# MicroMySens-v015.net
KiCad netlist of a schematic drawn in EAGLE
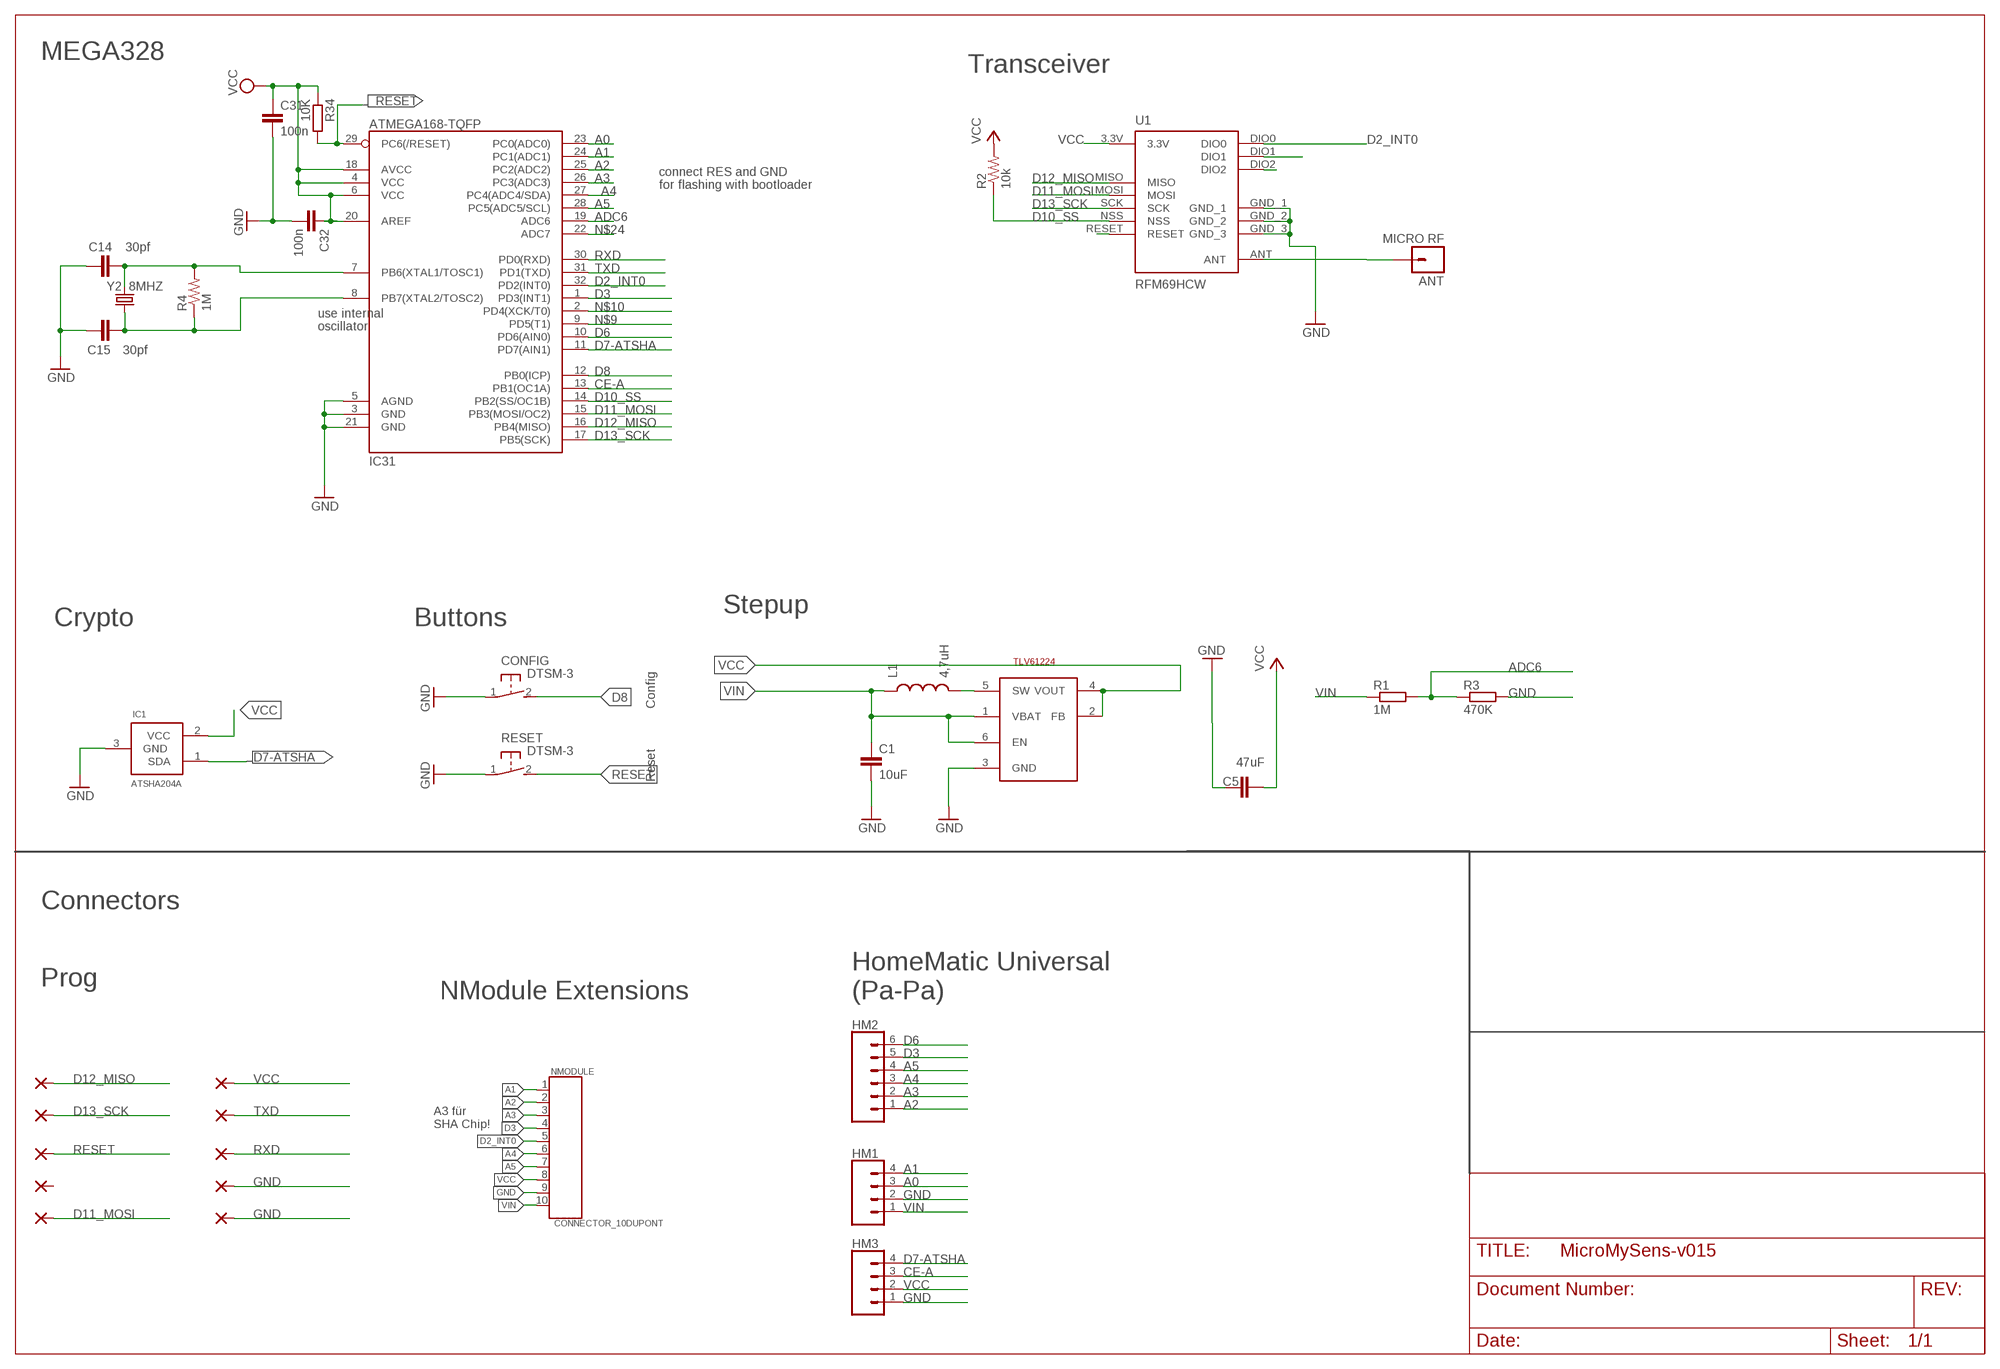
[diagram p0: schematic, sheet 1]

(export (version "E")
  (design (tool "Eeschema 10.0.6"))
  (components
    (comp (ref "ANT")
      (value "MICRO RF")
      (footprint "eagle-import:1X01")
      (libsource (lib "eagle-import") (part "M01PTH"))
    )
    (comp (ref "C1")
      (value "10uF")
      (footprint "eagle-import:0805")
      (libsource (lib "eagle-import") (part "CAP0805"))
    )
    (comp (ref "C5")
      (value "47uF")
      (footprint "eagle-import:C1210")
      (libsource (lib "eagle-import") (part "C-EUC1210"))
    )
    (comp (ref "C14")
      (value "30pf")
      (footprint "eagle-import:0805")
      (libsource (lib "eagle-import") (part "doug_CAP0805"))
    )
    (comp (ref "C15")
      (value "30pf")
      (footprint "eagle-import:0805")
      (libsource (lib "eagle-import") (part "doug_CAP0805"))
    )
    (comp (ref "C31")
      (value "100n")
      (footprint "eagle-import:C0805")
      (libsource (lib "eagle-import") (part "C-EUC0805"))
    )
    (comp (ref "C32")
      (value "100n")
      (footprint "eagle-import:C0805")
      (libsource (lib "eagle-import") (part "C-EUC0805"))
    )
    (comp (ref "CONFIG")
      (value "DTSM-3")
      (footprint "eagle-import:DTSM-3")
      (libsource (lib "eagle-import") (part "DTSM-3"))
    )
    (comp (ref "GND")
      (value "WIREPADSMD1,27-254")
      (footprint "eagle-import:SMD1,27-2,54")
      (libsource (lib "eagle-import") (part "WIREPADSMD1,27-254"))
    )
    (comp (ref "GND2")
      (value "WIREPADSMD1,27-254")
      (footprint "eagle-import:SMD1,27-2,54")
      (libsource (lib "eagle-import") (part "WIREPADSMD1,27-254"))
    )
    (comp (ref "HM1")
      (value "CONN_04")
      (footprint "eagle-import:1X04")
      (libsource (lib "eagle-import") (part "CONN_04"))
    )
    (comp (ref "HM2")
      (value "CONN_06SILK_FEMALE_PTH")
      (footprint "eagle-import:1X06")
      (libsource (lib "eagle-import") (part "CONN_06SILK_FEMALE_PTH"))
    )
    (comp (ref "HM3")
      (value "CONN_04")
      (footprint "eagle-import:1X04")
      (libsource (lib "eagle-import") (part "CONN_04"))
    )
    (comp (ref "IC1")
      (value "ATSHA204A")
      (footprint "eagle-import:SOT23")
      (libsource (lib "eagle-import") (part "ATSHA204A"))
    )
    (comp (ref "IC31")
      (value "ATMEGA168-TQFP")
      (footprint "eagle-import:TQFP32-08")
      (libsource (lib "eagle-import") (part "ATMEGA168-TQFP"))
    )
    (comp (ref "L1")
      (value "4,7uH")
      (footprint "eagle-import:0805")
      (libsource (lib "eagle-import") (part "INDUCTOR0805"))
    )
    (comp (ref "MISO")
      (value "WIREPADSMD1,27-254")
      (footprint "eagle-import:SMD1,27-2,54")
      (libsource (lib "eagle-import") (part "WIREPADSMD1,27-254"))
    )
    (comp (ref "MOSI")
      (value "WIREPADSMD1,27-254")
      (footprint "eagle-import:SMD1,27-2,54")
      (libsource (lib "eagle-import") (part "WIREPADSMD1,27-254"))
    )
    (comp (ref "NC")
      (value "WIREPADSMD1,27-254")
      (footprint "eagle-import:SMD1,27-2,54")
      (libsource (lib "eagle-import") (part "WIREPADSMD1,27-254"))
    )
    (comp (ref "NMODULE")
      (value "CONNECTOR_10DUPONT")
      (footprint "eagle-import:DUPONT_10")
      (libsource (lib "eagle-import") (part "CONNECTOR_10DUPONT"))
    )
    (comp (ref "R1")
      (value "1M")
      (footprint "eagle-import:R0805")
      (libsource (lib "eagle-import") (part "R-EU_R0805"))
    )
    (comp (ref "R2")
      (value "10k")
      (footprint "eagle-import:0805")
      (libsource (lib "eagle-import") (part "RESISTOR0805-RES"))
    )
    (comp (ref "R3")
      (value "470K")
      (footprint "eagle-import:R0805")
      (libsource (lib "eagle-import") (part "R-EU_R0805"))
    )
    (comp (ref "R4")
      (value "1M")
      (footprint "eagle-import:0805")
      (libsource (lib "eagle-import") (part "RESISTOR0805-RES"))
    )
    (comp (ref "R34")
      (value "10K")
      (footprint "eagle-import:R0805")
      (libsource (lib "eagle-import") (part "R-EU_R0805"))
    )
    (comp (ref "RESET")
      (value "DTSM-3")
      (footprint "eagle-import:DTSM-3")
      (libsource (lib "eagle-import") (part "DTSM-3"))
    )
    (comp (ref "RST")
      (value "WIREPADSMD1,27-254")
      (footprint "eagle-import:SMD1,27-2,54")
      (libsource (lib "eagle-import") (part "WIREPADSMD1,27-254"))
    )
    (comp (ref "RXD")
      (value "WIREPADSMD1,27-254")
      (footprint "eagle-import:SMD1,27-2,54")
      (libsource (lib "eagle-import") (part "WIREPADSMD1,27-254"))
    )
    (comp (ref "SCK")
      (value "WIREPADSMD1,27-254")
      (footprint "eagle-import:SMD1,27-2,54")
      (libsource (lib "eagle-import") (part "WIREPADSMD1,27-254"))
    )
    (comp (ref "STEPUP")
      (value "TLV61224")
      (footprint "eagle-import:SOT23-6L")
      (libsource (lib "eagle-import") (part "TI-TLV61224"))
    )
    (comp (ref "TXD")
      (value "WIREPADSMD1,27-254")
      (footprint "eagle-import:SMD1,27-2,54")
      (libsource (lib "eagle-import") (part "WIREPADSMD1,27-254"))
    )
    (comp (ref "U1")
      (value "RFM69HCW")
      (footprint "eagle-import:RFM69HCW-XXXS2")
      (libsource (lib "eagle-import") (part "RFM69HCW"))
    )
    (comp (ref "VCC")
      (value "WIREPADSMD1,27-254")
      (footprint "eagle-import:SMD1,27-2,54")
      (libsource (lib "eagle-import") (part "WIREPADSMD1,27-254"))
    )
    (comp (ref "Y2")
      (value "8MHZ")
      (footprint "eagle-import:CRYSTAL-TXC-7A")
      (libsource (lib "eagle-import") (part "CRYSTALTXC-7A"))
    )
  )
  (nets
    (net (code "1") (name "/A0") (class "Default")
      (node (ref "HM1") (pin "3") (pinfunction "3_3") (pintype "passive"))
      (node (ref "IC31") (pin "23") (pinfunction "PC0(ADC0)_23") (pintype "bidirectional"))
    )
    (net (code "2") (name "/ADC6") (class "Default")
      (node (ref "IC31") (pin "19") (pinfunction "ADC6_19") (pintype "bidirectional"))
      (node (ref "R1") (pin "2") (pinfunction "2_2") (pintype "passive"))
      (node (ref "R3") (pin "1") (pinfunction "1_1") (pintype "passive"))
    )
    (net (code "3") (name "/CE-A") (class "Default")
      (node (ref "HM3") (pin "3") (pinfunction "3_3") (pintype "passive"))
      (node (ref "IC31") (pin "13") (pinfunction "PB1(OC1A)_13") (pintype "bidirectional"))
    )
    (net (code "4") (name "/D6") (class "Default")
      (node (ref "HM2") (pin "6") (pinfunction "6_6") (pintype "passive"))
      (node (ref "IC31") (pin "10") (pinfunction "PD6(AIN0)_10") (pintype "bidirectional"))
    )
    (net (code "5") (name "/D7-ATSHA") (class "Default")
      (node (ref "HM3") (pin "4") (pinfunction "4_4") (pintype "passive"))
      (node (ref "IC1") (pin "1") (pinfunction "SDA_1") (pintype "bidirectional"))
      (node (ref "IC31") (pin "11") (pinfunction "PD7(AIN1)_11") (pintype "bidirectional"))
    )
    (net (code "6") (name "/D10_SS") (class "Default")
      (node (ref "IC31") (pin "14") (pinfunction "PB2(SS/OC1B)_14") (pintype "bidirectional"))
      (node (ref "R2") (pin "1") (pinfunction "1_1") (pintype "passive"))
      (node (ref "U1") (pin "NSS") (pinfunction "NSS_NSS") (pintype "input"))
    )
    (net (code "7") (name "/D11_MOSI") (class "Default")
      (node (ref "IC31") (pin "15") (pinfunction "PB3(MOSI/OC2)_15") (pintype "bidirectional"))
      (node (ref "MOSI") (pin "1") (pinfunction "P_1") (pintype "passive"))
      (node (ref "U1") (pin "MOSI") (pinfunction "MOSI_MOSI") (pintype "input"))
    )
    (net (code "8") (name "/D12_MISO") (class "Default")
      (node (ref "IC31") (pin "16") (pinfunction "PB4(MISO)_16") (pintype "bidirectional"))
      (node (ref "MISO") (pin "1") (pinfunction "P_1") (pintype "passive"))
      (node (ref "U1") (pin "MISO") (pinfunction "MISO_MISO") (pintype "bidirectional"))
    )
    (net (code "9") (name "/D13_SCK") (class "Default")
      (node (ref "IC31") (pin "17") (pinfunction "PB5(SCK)_17") (pintype "bidirectional"))
      (node (ref "SCK") (pin "1") (pinfunction "P_1") (pintype "passive"))
      (node (ref "U1") (pin "SCK") (pinfunction "SCK_SCK") (pintype "input"))
    )
    (net (code "10") (name "/N$9") (class "Default")
      (node (ref "IC31") (pin "9") (pinfunction "PD5(T1)_9") (pintype "bidirectional"))
    )
    (net (code "11") (name "/N$10") (class "Default")
      (node (ref "IC31") (pin "2") (pinfunction "PD4(XCK/T0)_2") (pintype "bidirectional"))
    )
    (net (code "12") (name "/N$24") (class "Default")
      (node (ref "IC31") (pin "22") (pinfunction "ADC7_22") (pintype "bidirectional"))
    )
    (net (code "13") (name "/RXD") (class "Default")
      (node (ref "IC31") (pin "30") (pinfunction "PD0(RXD)_30") (pintype "bidirectional"))
      (node (ref "RXD") (pin "1") (pinfunction "P_1") (pintype "passive"))
    )
    (net (code "14") (name "/TXD") (class "Default")
      (node (ref "IC31") (pin "31") (pinfunction "PD1(TXD)_31") (pintype "bidirectional"))
      (node (ref "TXD") (pin "1") (pinfunction "P_1") (pintype "passive"))
    )
    (net (code "15") (name "A1") (class "Default")
      (node (ref "HM1") (pin "4") (pinfunction "4_4") (pintype "passive"))
      (node (ref "IC31") (pin "24") (pinfunction "PC1(ADC1)_24") (pintype "bidirectional"))
      (node (ref "NMODULE") (pin "1") (pinfunction "1_1") (pintype "bidirectional"))
    )
    (net (code "16") (name "A2") (class "Default")
      (node (ref "HM2") (pin "1") (pinfunction "1_1") (pintype "passive"))
      (node (ref "IC31") (pin "25") (pinfunction "PC2(ADC2)_25") (pintype "bidirectional"))
      (node (ref "NMODULE") (pin "2") (pinfunction "2_2") (pintype "bidirectional"))
    )
    (net (code "17") (name "A3") (class "Default")
      (node (ref "HM2") (pin "2") (pinfunction "2_2") (pintype "passive"))
      (node (ref "IC31") (pin "26") (pinfunction "PC3(ADC3)_26") (pintype "bidirectional"))
      (node (ref "NMODULE") (pin "3") (pinfunction "3_3") (pintype "bidirectional"))
    )
    (net (code "18") (name "A4") (class "Default")
      (node (ref "HM2") (pin "3") (pinfunction "3_3") (pintype "passive"))
      (node (ref "IC31") (pin "27") (pinfunction "PC4(ADC4/SDA)_27") (pintype "bidirectional"))
      (node (ref "NMODULE") (pin "6") (pinfunction "6_6") (pintype "bidirectional"))
    )
    (net (code "19") (name "A5") (class "Default")
      (node (ref "HM2") (pin "4") (pinfunction "4_4") (pintype "passive"))
      (node (ref "IC31") (pin "28") (pinfunction "PC5(ADC5/SCL)_28") (pintype "bidirectional"))
      (node (ref "NMODULE") (pin "7") (pinfunction "7_7") (pintype "bidirectional"))
    )
    (net (code "20") (name "D2_INT0") (class "Default")
      (node (ref "IC31") (pin "32") (pinfunction "PD2(INT0)_32") (pintype "bidirectional"))
      (node (ref "NMODULE") (pin "5") (pinfunction "5_5") (pintype "bidirectional"))
      (node (ref "U1") (pin "DIO0") (pinfunction "DIO0_DIO0") (pintype "bidirectional"))
    )
    (net (code "21") (name "D3") (class "Default")
      (node (ref "HM2") (pin "5") (pinfunction "5_5") (pintype "passive"))
      (node (ref "IC31") (pin "1") (pinfunction "PD3(INT1)_1") (pintype "bidirectional"))
      (node (ref "NMODULE") (pin "4") (pinfunction "4_4") (pintype "bidirectional"))
    )
    (net (code "22") (name "D8") (class "Default")
      (node (ref "CONFIG") (pin "2") (pinfunction "2_2") (pintype "passive"))
      (node (ref "IC31") (pin "12") (pinfunction "PB0(ICP)_12") (pintype "bidirectional"))
    )
    (net (code "23") (name "GND") (class "Default")
      (node (ref "C1") (pin "2") (pinfunction "2_2") (pintype "passive"))
      (node (ref "C14") (pin "1") (pinfunction "1_1") (pintype "passive"))
      (node (ref "C15") (pin "1") (pinfunction "1_1") (pintype "passive"))
      (node (ref "C31") (pin "2") (pinfunction "2_2") (pintype "passive"))
      (node (ref "C32") (pin "2") (pinfunction "2_2") (pintype "passive"))
      (node (ref "C5") (pin "1") (pinfunction "1_1") (pintype "passive"))
      (node (ref "CONFIG") (pin "1") (pinfunction "1_1") (pintype "passive"))
      (node (ref "GND") (pin "1") (pinfunction "P_1") (pintype "passive"))
      (node (ref "GND2") (pin "1") (pinfunction "P_1") (pintype "passive"))
      (node (ref "HM1") (pin "2") (pinfunction "2_2") (pintype "passive"))
      (node (ref "HM3") (pin "1") (pinfunction "1_1") (pintype "passive"))
      (node (ref "IC1") (pin "3") (pinfunction "GND_3") (pintype "bidirectional"))
      (node (ref "IC31") (pin "21") (pinfunction "GND_21") (pintype "bidirectional"))
      (node (ref "IC31") (pin "3") (pinfunction "GND_3") (pintype "bidirectional"))
      (node (ref "IC31") (pin "5") (pinfunction "AGND_5") (pintype "bidirectional"))
      (node (ref "NMODULE") (pin "9") (pinfunction "9_9") (pintype "bidirectional"))
      (node (ref "R3") (pin "2") (pinfunction "2_2") (pintype "passive"))
      (node (ref "RESET") (pin "1") (pinfunction "1_1") (pintype "passive"))
      (node (ref "STEPUP") (pin "3") (pinfunction "GND_3") (pintype "power_in"))
      (node (ref "U1") (pin "GND_1") (pinfunction "GND_1_GND_1") (pintype "power_in"))
      (node (ref "U1") (pin "GND_2") (pinfunction "GND_2_GND_2") (pintype "power_in"))
      (node (ref "U1") (pin "GND_3") (pinfunction "GND_3_GND_3") (pintype "power_in"))
    )
    (net (code "24") (name "Net-(ANT-Pad1)") (class "Default")
      (node (ref "ANT") (pin "1") (pinfunction "1_1") (pintype "passive"))
      (node (ref "U1") (pin "ANT") (pinfunction "ANT_ANT") (pintype "passive"))
    )
    (net (code "25") (name "Net-(IC31-PB6(XTAL1{slash}TOSC1))") (class "Default")
      (node (ref "C14") (pin "2") (pinfunction "2_2") (pintype "passive"))
      (node (ref "IC31") (pin "7") (pinfunction "PB6(XTAL1/TOSC1)_7") (pintype "bidirectional"))
      (node (ref "R4") (pin "2") (pinfunction "2_2") (pintype "passive"))
      (node (ref "Y2") (pin "P$2") (pinfunction "2_P$2") (pintype "passive"))
    )
    (net (code "26") (name "Net-(IC31-PB7(XTAL2{slash}TOSC2))") (class "Default")
      (node (ref "C15") (pin "2") (pinfunction "2_2") (pintype "passive"))
      (node (ref "IC31") (pin "8") (pinfunction "PB7(XTAL2/TOSC2)_8") (pintype "bidirectional"))
      (node (ref "R4") (pin "1") (pinfunction "1_1") (pintype "passive"))
      (node (ref "Y2") (pin "P$1") (pinfunction "1_P$1") (pintype "passive"))
    )
    (net (code "27") (name "Net-(STEPUP-SW)") (class "Default")
      (node (ref "L1") (pin "2") (pinfunction "2_2") (pintype "passive"))
      (node (ref "STEPUP") (pin "5") (pinfunction "SW_5") (pintype "power_in"))
    )
    (net (code "28") (name "RESET") (class "Default")
      (node (ref "IC31") (pin "29") (pinfunction "PC6(/RESET)_29") (pintype "bidirectional"))
      (node (ref "R34") (pin "2") (pinfunction "2_2") (pintype "passive"))
      (node (ref "RESET") (pin "2") (pinfunction "2_2") (pintype "passive"))
      (node (ref "RST") (pin "1") (pinfunction "P_1") (pintype "passive"))
    )
    (net (code "29") (name "VCC") (class "Default")
      (node (ref "C31") (pin "1") (pinfunction "1_1") (pintype "passive"))
      (node (ref "C32") (pin "1") (pinfunction "1_1") (pintype "passive"))
      (node (ref "C5") (pin "2") (pinfunction "2_2") (pintype "passive"))
      (node (ref "HM3") (pin "2") (pinfunction "2_2") (pintype "passive"))
      (node (ref "IC1") (pin "2") (pinfunction "VCC_2") (pintype "bidirectional"))
      (node (ref "IC31") (pin "18") (pinfunction "AVCC_18") (pintype "bidirectional"))
      (node (ref "IC31") (pin "20") (pinfunction "AREF_20") (pintype "bidirectional"))
      (node (ref "IC31") (pin "4") (pinfunction "VCC_4") (pintype "bidirectional"))
      (node (ref "IC31") (pin "6") (pinfunction "VCC_6") (pintype "bidirectional"))
      (node (ref "NMODULE") (pin "8") (pinfunction "8_8") (pintype "bidirectional"))
      (node (ref "R2") (pin "2") (pinfunction "2_2") (pintype "passive"))
      (node (ref "R34") (pin "1") (pinfunction "1_1") (pintype "passive"))
      (node (ref "STEPUP") (pin "2") (pinfunction "FB_2") (pintype "input"))
      (node (ref "STEPUP") (pin "4") (pinfunction "VOUT_4") (pintype "power_in"))
      (node (ref "U1") (pin "3.3V") (pinfunction "3.3V_3.3V") (pintype "power_in"))
      (node (ref "VCC") (pin "1") (pinfunction "P_1") (pintype "passive"))
    )
    (net (code "30") (name "VIN") (class "Default")
      (node (ref "C1") (pin "1") (pinfunction "1_1") (pintype "passive"))
      (node (ref "HM1") (pin "1") (pinfunction "1_1") (pintype "passive"))
      (node (ref "L1") (pin "1") (pinfunction "1_1") (pintype "passive"))
      (node (ref "NMODULE") (pin "10") (pinfunction "10_10") (pintype "bidirectional"))
      (node (ref "R1") (pin "1") (pinfunction "1_1") (pintype "passive"))
      (node (ref "STEPUP") (pin "1") (pinfunction "VBAT_1") (pintype "power_in"))
      (node (ref "STEPUP") (pin "6") (pinfunction "EN_6") (pintype "input"))
    )
    (net (code "31") (name "unconnected-(NC-P-Pad1)") (class "Default")
      (node (ref "NC") (pin "1") (pinfunction "P_1") (pintype "passive"))
    )
    (net (code "32") (name "unconnected-(U1-PadDIO1)") (class "Default")
      (node (ref "U1") (pin "DIO1") (pinfunction "DIO1_DIO1") (pintype "bidirectional"))
    )
    (net (code "33") (name "unconnected-(U1-PadDIO2)") (class "Default")
      (node (ref "U1") (pin "DIO2") (pinfunction "DIO2_DIO2") (pintype "bidirectional"))
    )
    (net (code "34") (name "unconnected-(U1-PadRESET)") (class "Default")
      (node (ref "U1") (pin "RESET") (pinfunction "RESET_RESET") (pintype "input"))
    )
  )
)
